# Power.net
KiCad netlist of a schematic drawn in Altium Designer
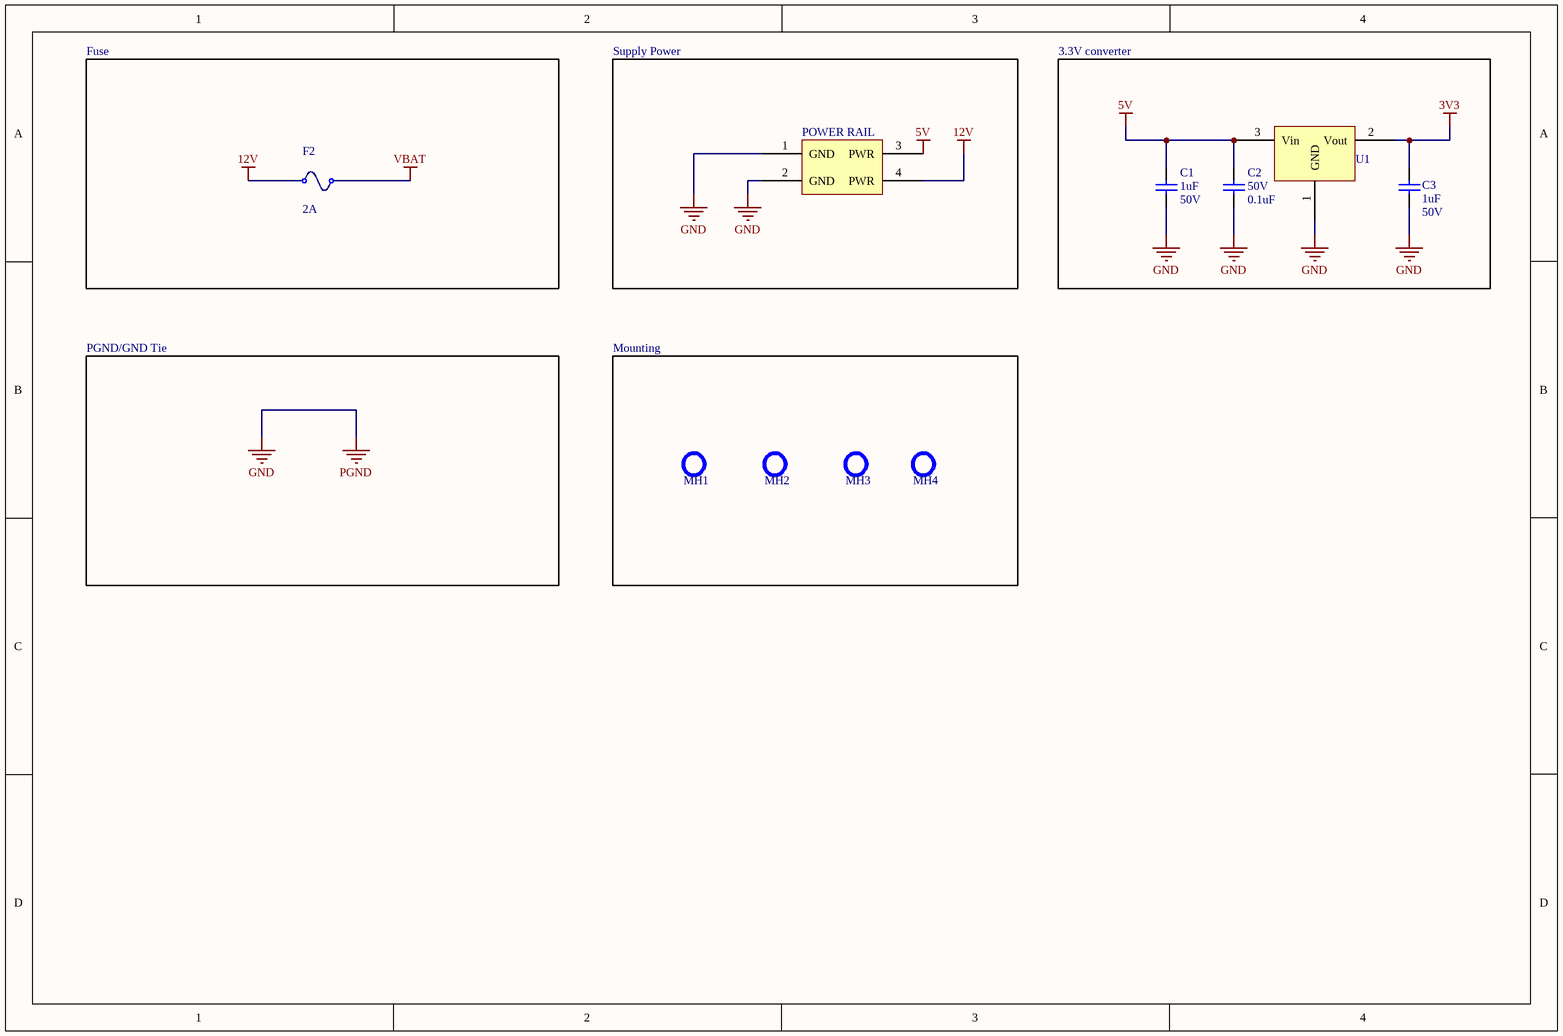
[diagram p0: Power.SchDoc]

(export (version "E")
  (design (tool "Eeschema 10.0.6"))
  (components
    (comp (ref "C1")
      (value "CL21B105KBFNNNG")
      (footprint "0803 CAP")
      (description "SAMSUNG ELECTRO-MECHANICS - CL21B105KBFNNNG - MLCC CAPACITORS")
      (fields
        (field (name "CAPACITANCE") "1uF")
        (field (name "TOLERANCE") "10%")
        (field (name "VOLTAGE") "50V")
      )
      (libsource (lib "") (part "Symbol_1"))
    )
    (comp (ref "C2")
      (value "CL10B104JB8NNNC")
      (footprint "FP-CL10-0_1-IPC_A")
      (description "CAP CER 0.1UF 50V X7R 0603")
      (fields
        (field (name "TOLERANCE") "5%")
        (field (name "VOLTAGE") "50V")
        (field (name "CAPACITANCE") "0.1uF")
      )
      (libsource (lib "AUVIC") (part "CAP-NP-2"))
    )
    (comp (ref "C3")
      (value "CL21B105KBFNNNG")
      (footprint "0803 CAP")
      (description "SAMSUNG ELECTRO-MECHANICS - CL21B105KBFNNNG - MLCC CAPACITORS")
      (fields
        (field (name "CAPACITANCE") "1uF")
        (field (name "TOLERANCE") "10%")
        (field (name "VOLTAGE") "50V")
      )
      (libsource (lib "") (part "Symbol_1"))
    )
    (comp (ref "F2")
      (value "SMD Fuse, 2A, 63VAC, Slow Blow")
      (footprint "RESC1206(3216)")
      (description "Fuse, Smd, 2A, Slow Blow, 1206")
      (fields (field (name "CURRENT RATING") "2A"))
      (libsource (lib "AUVIC") (part "Symbol"))
    )
    (comp (ref "MH1")
      (value "Mounting Hole, M3, Unplated")
      (footprint "Clearance_M3_UNPLATED")
      (fields
        (field (name "CREATED BY") "Ashwin Sira")
        (field (name "PUBLISHER") "AUVic")
        (field (name "SOURCE") "AUVic_Integrated_Library_Virtual_Components.SchLib")
      )
      (libsource (lib "AUVIC") (part "Mounting Hole, M3, Unplated"))
    )
    (comp (ref "MH2")
      (value "Mounting Hole, M3, Unplated")
      (footprint "Clearance_M3_UNPLATED")
      (fields
        (field (name "CREATED BY") "Ashwin Sira")
        (field (name "PUBLISHER") "AUVic")
        (field (name "SOURCE") "AUVic_Integrated_Library_Virtual_Components.SchLib")
      )
      (libsource (lib "AUVIC") (part "Mounting Hole, M3, Unplated"))
    )
    (comp (ref "MH3")
      (value "Mounting Hole, M3, Unplated")
      (footprint "Clearance_M3_UNPLATED")
      (fields
        (field (name "CREATED BY") "Ashwin Sira")
        (field (name "PUBLISHER") "AUVic")
        (field (name "SOURCE") "AUVic_Integrated_Library_Virtual_Components.SchLib")
      )
      (libsource (lib "AUVIC") (part "Mounting Hole, M3, Unplated"))
    )
    (comp (ref "MH4")
      (value "Mounting Hole, M3, Unplated")
      (footprint "Clearance_M3_UNPLATED")
      (fields
        (field (name "CREATED BY") "Ashwin Sira")
        (field (name "PUBLISHER") "AUVic")
        (field (name "SOURCE") "AUVic_Integrated_Library_Virtual_Components.SchLib")
      )
      (libsource (lib "AUVIC") (part "Mounting Hole, M3, Unplated"))
    )
    (comp (ref "POWER RAIL")
      (value "Header, Female, 2x2, RIght Angle, Pitch: 0.118\"  (3.00mm), THT")
      (footprint "2x2 Pitch 118mil connector")
      (description "Connector Header Through Hole, Right Angle 4 position 0.118\" (3.00mm)")
      (fields
        (field (name "PUBLISHER") "AUVic")
        (field (name "CREATED BY") "Poorna Chander Kalidas")
        (field (name "SOURCE") "AUVic_Schematic_Library_Connectors.SchLib")
      )
      (libsource (lib "AUVIC") (part "Header, Female, 2x2, RIght Angle, Pitch{colon} 0.118{dblquote}  (3.00mm), THT"))
    )
    (comp (ref "U1")
      (value "3.3V 250mA Linear Reg LDO")
      (footprint "SOT95P245X110-3N")
      (description "IC REG LINEAR 3.3V 250MA SOT23-3")
      (fields (field (name "CREATED BY") "Poorna Chander Kalidas"))
      (libsource (lib "AUVIC") (part "3.3V 250mA Linear Reg LDO"))
    )
  )
  (nets
    (net (code "1") (name "3V3") (class "Default")
      (node (ref "C3") (pin "2") (pinfunction "2_2") (pintype "passive"))
      (node (ref "U1") (pin "2") (pinfunction "Vout_2") (pintype "power_in"))
    )
    (net (code "2") (name "5V") (class "Default")
      (node (ref "C1") (pin "2") (pinfunction "2_2") (pintype "passive"))
      (node (ref "C2") (pin "2") (pinfunction "2_2") (pintype "passive"))
      (node (ref "POWER RAIL") (pin "3") (pinfunction "PWR_3") (pintype "passive"))
      (node (ref "U1") (pin "3") (pinfunction "Vin_3") (pintype "power_in"))
    )
    (net (code "3") (name "12V") (class "Default")
      (node (ref "F2") (pin "1") (pinfunction "1_1") (pintype "passive"))
      (node (ref "POWER RAIL") (pin "4") (pinfunction "PWR_4") (pintype "passive"))
    )
    (net (code "4") (name "GND") (class "Default")
      (node (ref "C1") (pin "1") (pinfunction "1_1") (pintype "passive"))
      (node (ref "C2") (pin "1") (pinfunction "1_1") (pintype "passive"))
      (node (ref "C3") (pin "1") (pinfunction "1_1") (pintype "passive"))
      (node (ref "POWER RAIL") (pin "1") (pinfunction "GND_1") (pintype "passive"))
      (node (ref "POWER RAIL") (pin "2") (pinfunction "GND_2") (pintype "passive"))
      (node (ref "U1") (pin "1") (pinfunction "GND_1") (pintype "power_in"))
    )
    (net (code "5") (name "VBAT") (class "Default")
      (node (ref "F2") (pin "2") (pinfunction "2_2") (pintype "passive"))
    )
  )
)
